# AVRI2CIO_V0_2_LEVEL0.net
KiCad netlist of a schematic drawn in EAGLE
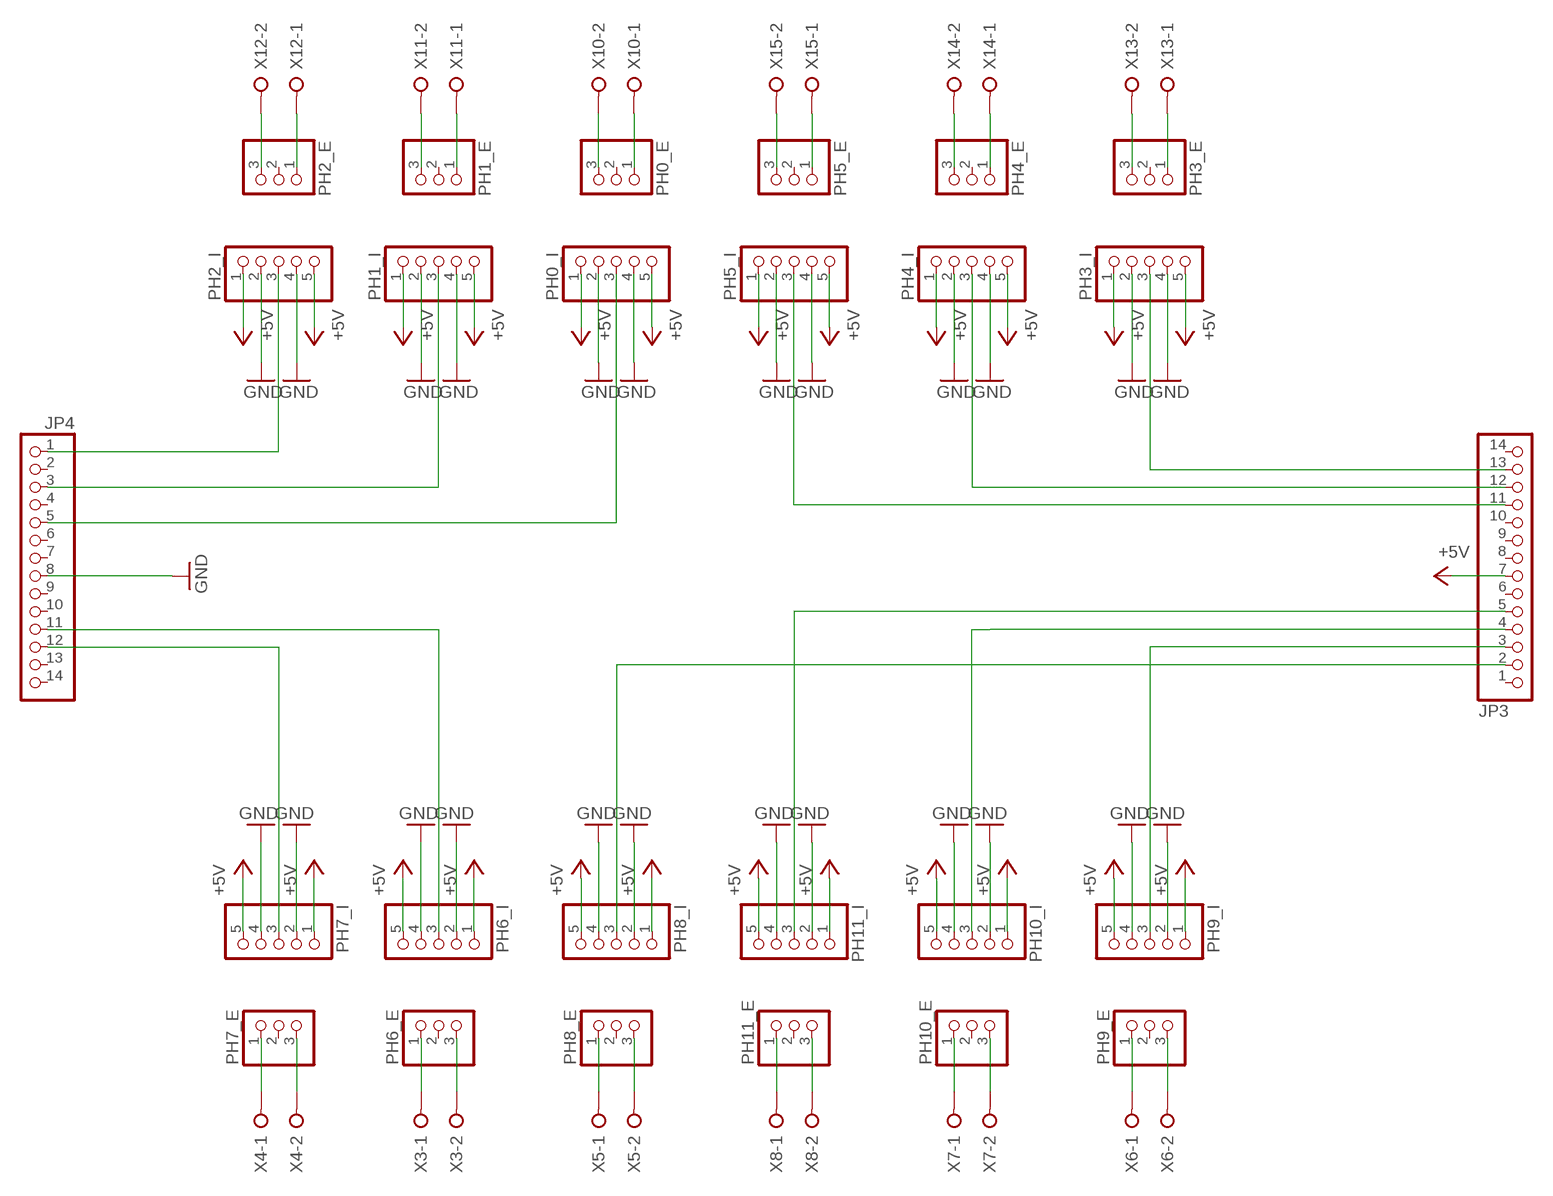
[diagram p0: schematic, sheet 1]

(export (version "E")
  (design (tool "Eeschema 10.0.6"))
  (components
    (comp (ref "JP3")
      (value "PINHD-1X14")
      (footprint "eagle-import:1X14")
      (libsource (lib "eagle-import") (part "PINHD-1X14"))
    )
    (comp (ref "JP4")
      (value "PINHD-1X14")
      (footprint "eagle-import:1X14")
      (libsource (lib "eagle-import") (part "PINHD-1X14"))
    )
    (comp (ref "PH0_E")
      (value "PINHD-1X3")
      (footprint "eagle-import:1X03")
      (libsource (lib "eagle-import") (part "PINHD-1X3"))
    )
    (comp (ref "PH0_I")
      (value "PINHD-1X5")
      (footprint "eagle-import:1X05")
      (libsource (lib "eagle-import") (part "PINHD-1X5"))
    )
    (comp (ref "PH1_E")
      (value "PINHD-1X3")
      (footprint "eagle-import:1X03")
      (libsource (lib "eagle-import") (part "PINHD-1X3"))
    )
    (comp (ref "PH1_I")
      (value "PINHD-1X5")
      (footprint "eagle-import:1X05")
      (libsource (lib "eagle-import") (part "PINHD-1X5"))
    )
    (comp (ref "PH2_E")
      (value "PINHD-1X3")
      (footprint "eagle-import:1X03")
      (libsource (lib "eagle-import") (part "PINHD-1X3"))
    )
    (comp (ref "PH2_I")
      (value "PINHD-1X5")
      (footprint "eagle-import:1X05")
      (libsource (lib "eagle-import") (part "PINHD-1X5"))
    )
    (comp (ref "PH3_E")
      (value "PINHD-1X3")
      (footprint "eagle-import:1X03")
      (libsource (lib "eagle-import") (part "PINHD-1X3"))
    )
    (comp (ref "PH3_I")
      (value "PINHD-1X5")
      (footprint "eagle-import:1X05")
      (libsource (lib "eagle-import") (part "PINHD-1X5"))
    )
    (comp (ref "PH4_E")
      (value "PINHD-1X3")
      (footprint "eagle-import:1X03")
      (libsource (lib "eagle-import") (part "PINHD-1X3"))
    )
    (comp (ref "PH4_I")
      (value "PINHD-1X5")
      (footprint "eagle-import:1X05")
      (libsource (lib "eagle-import") (part "PINHD-1X5"))
    )
    (comp (ref "PH5_E")
      (value "PINHD-1X3")
      (footprint "eagle-import:1X03")
      (libsource (lib "eagle-import") (part "PINHD-1X3"))
    )
    (comp (ref "PH5_I")
      (value "PINHD-1X5")
      (footprint "eagle-import:1X05")
      (libsource (lib "eagle-import") (part "PINHD-1X5"))
    )
    (comp (ref "PH6_E")
      (value "PINHD-1X3")
      (footprint "eagle-import:1X03")
      (libsource (lib "eagle-import") (part "PINHD-1X3"))
    )
    (comp (ref "PH6_I")
      (value "PINHD-1X5")
      (footprint "eagle-import:1X05")
      (libsource (lib "eagle-import") (part "PINHD-1X5"))
    )
    (comp (ref "PH7_E")
      (value "PINHD-1X3")
      (footprint "eagle-import:1X03")
      (libsource (lib "eagle-import") (part "PINHD-1X3"))
    )
    (comp (ref "PH7_I")
      (value "PINHD-1X5")
      (footprint "eagle-import:1X05")
      (libsource (lib "eagle-import") (part "PINHD-1X5"))
    )
    (comp (ref "PH8_E")
      (value "PINHD-1X3")
      (footprint "eagle-import:1X03")
      (libsource (lib "eagle-import") (part "PINHD-1X3"))
    )
    (comp (ref "PH8_I")
      (value "PINHD-1X5")
      (footprint "eagle-import:1X05")
      (libsource (lib "eagle-import") (part "PINHD-1X5"))
    )
    (comp (ref "PH9_E")
      (value "PINHD-1X3")
      (footprint "eagle-import:1X03")
      (libsource (lib "eagle-import") (part "PINHD-1X3"))
    )
    (comp (ref "PH9_I")
      (value "PINHD-1X5")
      (footprint "eagle-import:1X05")
      (libsource (lib "eagle-import") (part "PINHD-1X5"))
    )
    (comp (ref "PH10_E")
      (value "PINHD-1X3")
      (footprint "eagle-import:1X03")
      (libsource (lib "eagle-import") (part "PINHD-1X3"))
    )
    (comp (ref "PH10_I")
      (value "PINHD-1X5")
      (footprint "eagle-import:1X05")
      (libsource (lib "eagle-import") (part "PINHD-1X5"))
    )
    (comp (ref "PH11_E")
      (value "PINHD-1X3")
      (footprint "eagle-import:1X03")
      (libsource (lib "eagle-import") (part "PINHD-1X3"))
    )
    (comp (ref "PH11_I")
      (value "PINHD-1X5")
      (footprint "eagle-import:1X05")
      (libsource (lib "eagle-import") (part "PINHD-1X5"))
    )
    (comp (ref "X3")
      (value "W237-02P")
      (footprint "eagle-import:W237-132")
      (libsource (lib "eagle-import") (part "W237-02P"))
    )
    (comp (ref "X4")
      (value "W237-02P")
      (footprint "eagle-import:W237-132")
      (libsource (lib "eagle-import") (part "W237-02P"))
    )
    (comp (ref "X5")
      (value "W237-02P")
      (footprint "eagle-import:W237-132")
      (libsource (lib "eagle-import") (part "W237-02P"))
    )
    (comp (ref "X6")
      (value "W237-02P")
      (footprint "eagle-import:W237-132")
      (libsource (lib "eagle-import") (part "W237-02P"))
    )
    (comp (ref "X7")
      (value "W237-02P")
      (footprint "eagle-import:W237-132")
      (libsource (lib "eagle-import") (part "W237-02P"))
    )
    (comp (ref "X8")
      (value "W237-02P")
      (footprint "eagle-import:W237-132")
      (libsource (lib "eagle-import") (part "W237-02P"))
    )
    (comp (ref "X10")
      (value "W237-02P")
      (footprint "eagle-import:W237-132")
      (fields (field (name "OC_FARNELL") "unknown"))
      (libsource (lib "eagle-import") (part "W237-02P"))
    )
    (comp (ref "X11")
      (value "W237-02P")
      (footprint "eagle-import:W237-132")
      (libsource (lib "eagle-import") (part "W237-02P"))
    )
    (comp (ref "X12")
      (value "W237-02P")
      (footprint "eagle-import:W237-132")
      (libsource (lib "eagle-import") (part "W237-02P"))
    )
    (comp (ref "X13")
      (value "W237-02P")
      (footprint "eagle-import:W237-132")
      (libsource (lib "eagle-import") (part "W237-02P"))
    )
    (comp (ref "X14")
      (value "W237-02P")
      (footprint "eagle-import:W237-132")
      (libsource (lib "eagle-import") (part "W237-02P"))
    )
    (comp (ref "X15")
      (value "W237-02P")
      (footprint "eagle-import:W237-132")
      (libsource (lib "eagle-import") (part "W237-02P"))
    )
  )
  (nets
    (net (code "1") (name "+5V") (class "Default")
      (node (ref "JP3") (pin "7") (pinfunction "7_7") (pintype "passive"))
      (node (ref "PH0_I") (pin "1") (pinfunction "1_1") (pintype "passive"))
      (node (ref "PH0_I") (pin "5") (pinfunction "5_5") (pintype "passive"))
      (node (ref "PH10_I") (pin "1") (pinfunction "1_1") (pintype "passive"))
      (node (ref "PH10_I") (pin "5") (pinfunction "5_5") (pintype "passive"))
      (node (ref "PH11_I") (pin "1") (pinfunction "1_1") (pintype "passive"))
      (node (ref "PH11_I") (pin "5") (pinfunction "5_5") (pintype "passive"))
      (node (ref "PH1_I") (pin "1") (pinfunction "1_1") (pintype "passive"))
      (node (ref "PH1_I") (pin "5") (pinfunction "5_5") (pintype "passive"))
      (node (ref "PH2_I") (pin "1") (pinfunction "1_1") (pintype "passive"))
      (node (ref "PH2_I") (pin "5") (pinfunction "5_5") (pintype "passive"))
      (node (ref "PH3_I") (pin "1") (pinfunction "1_1") (pintype "passive"))
      (node (ref "PH3_I") (pin "5") (pinfunction "5_5") (pintype "passive"))
      (node (ref "PH4_I") (pin "1") (pinfunction "1_1") (pintype "passive"))
      (node (ref "PH4_I") (pin "5") (pinfunction "5_5") (pintype "passive"))
      (node (ref "PH5_I") (pin "1") (pinfunction "1_1") (pintype "passive"))
      (node (ref "PH5_I") (pin "5") (pinfunction "5_5") (pintype "passive"))
      (node (ref "PH6_I") (pin "1") (pinfunction "1_1") (pintype "passive"))
      (node (ref "PH6_I") (pin "5") (pinfunction "5_5") (pintype "passive"))
      (node (ref "PH7_I") (pin "1") (pinfunction "1_1") (pintype "passive"))
      (node (ref "PH7_I") (pin "5") (pinfunction "5_5") (pintype "passive"))
      (node (ref "PH8_I") (pin "1") (pinfunction "1_1") (pintype "passive"))
      (node (ref "PH8_I") (pin "5") (pinfunction "5_5") (pintype "passive"))
      (node (ref "PH9_I") (pin "1") (pinfunction "1_1") (pintype "passive"))
      (node (ref "PH9_I") (pin "5") (pinfunction "5_5") (pintype "passive"))
    )
    (net (code "2") (name "GND") (class "Default")
      (node (ref "JP4") (pin "8") (pinfunction "8_8") (pintype "passive"))
      (node (ref "PH0_I") (pin "2") (pinfunction "2_2") (pintype "passive"))
      (node (ref "PH0_I") (pin "4") (pinfunction "4_4") (pintype "passive"))
      (node (ref "PH10_I") (pin "2") (pinfunction "2_2") (pintype "passive"))
      (node (ref "PH10_I") (pin "4") (pinfunction "4_4") (pintype "passive"))
      (node (ref "PH11_I") (pin "2") (pinfunction "2_2") (pintype "passive"))
      (node (ref "PH11_I") (pin "4") (pinfunction "4_4") (pintype "passive"))
      (node (ref "PH1_I") (pin "2") (pinfunction "2_2") (pintype "passive"))
      (node (ref "PH1_I") (pin "4") (pinfunction "4_4") (pintype "passive"))
      (node (ref "PH2_I") (pin "2") (pinfunction "2_2") (pintype "passive"))
      (node (ref "PH2_I") (pin "4") (pinfunction "4_4") (pintype "passive"))
      (node (ref "PH3_I") (pin "2") (pinfunction "2_2") (pintype "passive"))
      (node (ref "PH3_I") (pin "4") (pinfunction "4_4") (pintype "passive"))
      (node (ref "PH4_I") (pin "2") (pinfunction "2_2") (pintype "passive"))
      (node (ref "PH4_I") (pin "4") (pinfunction "4_4") (pintype "passive"))
      (node (ref "PH5_I") (pin "2") (pinfunction "2_2") (pintype "passive"))
      (node (ref "PH5_I") (pin "4") (pinfunction "4_4") (pintype "passive"))
      (node (ref "PH6_I") (pin "2") (pinfunction "2_2") (pintype "passive"))
      (node (ref "PH6_I") (pin "4") (pinfunction "4_4") (pintype "passive"))
      (node (ref "PH7_I") (pin "2") (pinfunction "2_2") (pintype "passive"))
      (node (ref "PH7_I") (pin "4") (pinfunction "4_4") (pintype "passive"))
      (node (ref "PH8_I") (pin "2") (pinfunction "2_2") (pintype "passive"))
      (node (ref "PH8_I") (pin "4") (pinfunction "4_4") (pintype "passive"))
      (node (ref "PH9_I") (pin "2") (pinfunction "2_2") (pintype "passive"))
      (node (ref "PH9_I") (pin "4") (pinfunction "4_4") (pintype "passive"))
    )
    (net (code "3") (name "Net-(JP3-Pad2)") (class "Default")
      (node (ref "JP3") (pin "2") (pinfunction "2_2") (pintype "passive"))
      (node (ref "PH8_I") (pin "3") (pinfunction "3_3") (pintype "passive"))
    )
    (net (code "4") (name "Net-(JP3-Pad3)") (class "Default")
      (node (ref "JP3") (pin "3") (pinfunction "3_3") (pintype "passive"))
      (node (ref "PH9_I") (pin "3") (pinfunction "3_3") (pintype "passive"))
    )
    (net (code "5") (name "Net-(JP3-Pad4)") (class "Default")
      (node (ref "JP3") (pin "4") (pinfunction "4_4") (pintype "passive"))
      (node (ref "PH10_I") (pin "3") (pinfunction "3_3") (pintype "passive"))
    )
    (net (code "6") (name "Net-(JP3-Pad5)") (class "Default")
      (node (ref "JP3") (pin "5") (pinfunction "5_5") (pintype "passive"))
      (node (ref "PH11_I") (pin "3") (pinfunction "3_3") (pintype "passive"))
    )
    (net (code "7") (name "Net-(JP3-Pad11)") (class "Default")
      (node (ref "JP3") (pin "11") (pinfunction "11_11") (pintype "passive"))
      (node (ref "PH5_I") (pin "3") (pinfunction "3_3") (pintype "passive"))
    )
    (net (code "8") (name "Net-(JP3-Pad12)") (class "Default")
      (node (ref "JP3") (pin "12") (pinfunction "12_12") (pintype "passive"))
      (node (ref "PH4_I") (pin "3") (pinfunction "3_3") (pintype "passive"))
    )
    (net (code "9") (name "Net-(JP3-Pad13)") (class "Default")
      (node (ref "JP3") (pin "13") (pinfunction "13_13") (pintype "passive"))
      (node (ref "PH3_I") (pin "3") (pinfunction "3_3") (pintype "passive"))
    )
    (net (code "10") (name "Net-(JP4-Pad1)") (class "Default")
      (node (ref "JP4") (pin "1") (pinfunction "1_1") (pintype "passive"))
      (node (ref "PH2_I") (pin "3") (pinfunction "3_3") (pintype "passive"))
    )
    (net (code "11") (name "Net-(JP4-Pad3)") (class "Default")
      (node (ref "JP4") (pin "3") (pinfunction "3_3") (pintype "passive"))
      (node (ref "PH1_I") (pin "3") (pinfunction "3_3") (pintype "passive"))
    )
    (net (code "12") (name "Net-(JP4-Pad5)") (class "Default")
      (node (ref "JP4") (pin "5") (pinfunction "5_5") (pintype "passive"))
      (node (ref "PH0_I") (pin "3") (pinfunction "3_3") (pintype "passive"))
    )
    (net (code "13") (name "Net-(JP4-Pad11)") (class "Default")
      (node (ref "JP4") (pin "11") (pinfunction "11_11") (pintype "passive"))
      (node (ref "PH6_I") (pin "3") (pinfunction "3_3") (pintype "passive"))
    )
    (net (code "14") (name "Net-(JP4-Pad12)") (class "Default")
      (node (ref "JP4") (pin "12") (pinfunction "12_12") (pintype "passive"))
      (node (ref "PH7_I") (pin "3") (pinfunction "3_3") (pintype "passive"))
    )
    (net (code "15") (name "Net-(X3A-KL)") (class "Default")
      (node (ref "PH6_E") (pin "1") (pinfunction "1_1") (pintype "passive"))
      (node (ref "X3") (pin "1") (pinfunction "KL_1") (pintype "passive"))
    )
    (net (code "16") (name "Net-(X3B-KL)") (class "Default")
      (node (ref "PH6_E") (pin "3") (pinfunction "3_3") (pintype "passive"))
      (node (ref "X3") (pin "2") (pinfunction "KL_2") (pintype "passive"))
    )
    (net (code "17") (name "Net-(X4A-KL)") (class "Default")
      (node (ref "PH7_E") (pin "1") (pinfunction "1_1") (pintype "passive"))
      (node (ref "X4") (pin "1") (pinfunction "KL_1") (pintype "passive"))
    )
    (net (code "18") (name "Net-(X4B-KL)") (class "Default")
      (node (ref "PH7_E") (pin "3") (pinfunction "3_3") (pintype "passive"))
      (node (ref "X4") (pin "2") (pinfunction "KL_2") (pintype "passive"))
    )
    (net (code "19") (name "Net-(X5A-KL)") (class "Default")
      (node (ref "PH8_E") (pin "1") (pinfunction "1_1") (pintype "passive"))
      (node (ref "X5") (pin "1") (pinfunction "KL_1") (pintype "passive"))
    )
    (net (code "20") (name "Net-(X5B-KL)") (class "Default")
      (node (ref "PH8_E") (pin "3") (pinfunction "3_3") (pintype "passive"))
      (node (ref "X5") (pin "2") (pinfunction "KL_2") (pintype "passive"))
    )
    (net (code "21") (name "Net-(X6A-KL)") (class "Default")
      (node (ref "PH9_E") (pin "1") (pinfunction "1_1") (pintype "passive"))
      (node (ref "X6") (pin "1") (pinfunction "KL_1") (pintype "passive"))
    )
    (net (code "22") (name "Net-(X6B-KL)") (class "Default")
      (node (ref "PH9_E") (pin "3") (pinfunction "3_3") (pintype "passive"))
      (node (ref "X6") (pin "2") (pinfunction "KL_2") (pintype "passive"))
    )
    (net (code "23") (name "Net-(X7A-KL)") (class "Default")
      (node (ref "PH10_E") (pin "1") (pinfunction "1_1") (pintype "passive"))
      (node (ref "X7") (pin "1") (pinfunction "KL_1") (pintype "passive"))
    )
    (net (code "24") (name "Net-(X7B-KL)") (class "Default")
      (node (ref "PH10_E") (pin "3") (pinfunction "3_3") (pintype "passive"))
      (node (ref "X7") (pin "2") (pinfunction "KL_2") (pintype "passive"))
    )
    (net (code "25") (name "Net-(X8A-KL)") (class "Default")
      (node (ref "PH11_E") (pin "1") (pinfunction "1_1") (pintype "passive"))
      (node (ref "X8") (pin "1") (pinfunction "KL_1") (pintype "passive"))
    )
    (net (code "26") (name "Net-(X8B-KL)") (class "Default")
      (node (ref "PH11_E") (pin "3") (pinfunction "3_3") (pintype "passive"))
      (node (ref "X8") (pin "2") (pinfunction "KL_2") (pintype "passive"))
    )
    (net (code "27") (name "Net-(X10A-KL)") (class "Default")
      (node (ref "PH0_E") (pin "1") (pinfunction "1_1") (pintype "passive"))
      (node (ref "X10") (pin "1") (pinfunction "KL_1") (pintype "passive"))
    )
    (net (code "28") (name "Net-(X10B-KL)") (class "Default")
      (node (ref "PH0_E") (pin "3") (pinfunction "3_3") (pintype "passive"))
      (node (ref "X10") (pin "2") (pinfunction "KL_2") (pintype "passive"))
    )
    (net (code "29") (name "Net-(X11A-KL)") (class "Default")
      (node (ref "PH1_E") (pin "1") (pinfunction "1_1") (pintype "passive"))
      (node (ref "X11") (pin "1") (pinfunction "KL_1") (pintype "passive"))
    )
    (net (code "30") (name "Net-(X11B-KL)") (class "Default")
      (node (ref "PH1_E") (pin "3") (pinfunction "3_3") (pintype "passive"))
      (node (ref "X11") (pin "2") (pinfunction "KL_2") (pintype "passive"))
    )
    (net (code "31") (name "Net-(X12A-KL)") (class "Default")
      (node (ref "PH2_E") (pin "1") (pinfunction "1_1") (pintype "passive"))
      (node (ref "X12") (pin "1") (pinfunction "KL_1") (pintype "passive"))
    )
    (net (code "32") (name "Net-(X12B-KL)") (class "Default")
      (node (ref "PH2_E") (pin "3") (pinfunction "3_3") (pintype "passive"))
      (node (ref "X12") (pin "2") (pinfunction "KL_2") (pintype "passive"))
    )
    (net (code "33") (name "Net-(X13A-KL)") (class "Default")
      (node (ref "PH3_E") (pin "1") (pinfunction "1_1") (pintype "passive"))
      (node (ref "X13") (pin "1") (pinfunction "KL_1") (pintype "passive"))
    )
    (net (code "34") (name "Net-(X13B-KL)") (class "Default")
      (node (ref "PH3_E") (pin "3") (pinfunction "3_3") (pintype "passive"))
      (node (ref "X13") (pin "2") (pinfunction "KL_2") (pintype "passive"))
    )
    (net (code "35") (name "Net-(X14A-KL)") (class "Default")
      (node (ref "PH4_E") (pin "1") (pinfunction "1_1") (pintype "passive"))
      (node (ref "X14") (pin "1") (pinfunction "KL_1") (pintype "passive"))
    )
    (net (code "36") (name "Net-(X14B-KL)") (class "Default")
      (node (ref "PH4_E") (pin "3") (pinfunction "3_3") (pintype "passive"))
      (node (ref "X14") (pin "2") (pinfunction "KL_2") (pintype "passive"))
    )
    (net (code "37") (name "Net-(X15A-KL)") (class "Default")
      (node (ref "PH5_E") (pin "1") (pinfunction "1_1") (pintype "passive"))
      (node (ref "X15") (pin "1") (pinfunction "KL_1") (pintype "passive"))
    )
    (net (code "38") (name "Net-(X15B-KL)") (class "Default")
      (node (ref "PH5_E") (pin "3") (pinfunction "3_3") (pintype "passive"))
      (node (ref "X15") (pin "2") (pinfunction "KL_2") (pintype "passive"))
    )
    (net (code "39") (name "unconnected-(JP3-Pad1)") (class "Default")
      (node (ref "JP3") (pin "1") (pinfunction "1_1") (pintype "passive"))
    )
    (net (code "40") (name "unconnected-(JP3-Pad6)") (class "Default")
      (node (ref "JP3") (pin "6") (pinfunction "6_6") (pintype "passive"))
    )
    (net (code "41") (name "unconnected-(JP3-Pad8)") (class "Default")
      (node (ref "JP3") (pin "8") (pinfunction "8_8") (pintype "passive"))
    )
    (net (code "42") (name "unconnected-(JP3-Pad9)") (class "Default")
      (node (ref "JP3") (pin "9") (pinfunction "9_9") (pintype "passive"))
    )
    (net (code "43") (name "unconnected-(JP3-Pad10)") (class "Default")
      (node (ref "JP3") (pin "10") (pinfunction "10_10") (pintype "passive"))
    )
    (net (code "44") (name "unconnected-(JP3-Pad14)") (class "Default")
      (node (ref "JP3") (pin "14") (pinfunction "14_14") (pintype "passive"))
    )
    (net (code "45") (name "unconnected-(JP4-Pad2)") (class "Default")
      (node (ref "JP4") (pin "2") (pinfunction "2_2") (pintype "passive"))
    )
    (net (code "46") (name "unconnected-(JP4-Pad4)") (class "Default")
      (node (ref "JP4") (pin "4") (pinfunction "4_4") (pintype "passive"))
    )
    (net (code "47") (name "unconnected-(JP4-Pad6)") (class "Default")
      (node (ref "JP4") (pin "6") (pinfunction "6_6") (pintype "passive"))
    )
    (net (code "48") (name "unconnected-(JP4-Pad7)") (class "Default")
      (node (ref "JP4") (pin "7") (pinfunction "7_7") (pintype "passive"))
    )
    (net (code "49") (name "unconnected-(JP4-Pad9)") (class "Default")
      (node (ref "JP4") (pin "9") (pinfunction "9_9") (pintype "passive"))
    )
    (net (code "50") (name "unconnected-(JP4-Pad10)") (class "Default")
      (node (ref "JP4") (pin "10") (pinfunction "10_10") (pintype "passive"))
    )
    (net (code "51") (name "unconnected-(JP4-Pad13)") (class "Default")
      (node (ref "JP4") (pin "13") (pinfunction "13_13") (pintype "passive"))
    )
    (net (code "52") (name "unconnected-(JP4-Pad14)") (class "Default")
      (node (ref "JP4") (pin "14") (pinfunction "14_14") (pintype "passive"))
    )
    (net (code "53") (name "unconnected-(PH0_E-Pad2)") (class "Default")
      (node (ref "PH0_E") (pin "2") (pinfunction "2_2") (pintype "passive"))
    )
    (net (code "54") (name "unconnected-(PH1_E-Pad2)") (class "Default")
      (node (ref "PH1_E") (pin "2") (pinfunction "2_2") (pintype "passive"))
    )
    (net (code "55") (name "unconnected-(PH2_E-Pad2)") (class "Default")
      (node (ref "PH2_E") (pin "2") (pinfunction "2_2") (pintype "passive"))
    )
    (net (code "56") (name "unconnected-(PH3_E-Pad2)") (class "Default")
      (node (ref "PH3_E") (pin "2") (pinfunction "2_2") (pintype "passive"))
    )
    (net (code "57") (name "unconnected-(PH4_E-Pad2)") (class "Default")
      (node (ref "PH4_E") (pin "2") (pinfunction "2_2") (pintype "passive"))
    )
    (net (code "58") (name "unconnected-(PH5_E-Pad2)") (class "Default")
      (node (ref "PH5_E") (pin "2") (pinfunction "2_2") (pintype "passive"))
    )
    (net (code "59") (name "unconnected-(PH6_E-Pad2)") (class "Default")
      (node (ref "PH6_E") (pin "2") (pinfunction "2_2") (pintype "passive"))
    )
    (net (code "60") (name "unconnected-(PH7_E-Pad2)") (class "Default")
      (node (ref "PH7_E") (pin "2") (pinfunction "2_2") (pintype "passive"))
    )
    (net (code "61") (name "unconnected-(PH8_E-Pad2)") (class "Default")
      (node (ref "PH8_E") (pin "2") (pinfunction "2_2") (pintype "passive"))
    )
    (net (code "62") (name "unconnected-(PH9_E-Pad2)") (class "Default")
      (node (ref "PH9_E") (pin "2") (pinfunction "2_2") (pintype "passive"))
    )
    (net (code "63") (name "unconnected-(PH10_E-Pad2)") (class "Default")
      (node (ref "PH10_E") (pin "2") (pinfunction "2_2") (pintype "passive"))
    )
    (net (code "64") (name "unconnected-(PH11_E-Pad2)") (class "Default")
      (node (ref "PH11_E") (pin "2") (pinfunction "2_2") (pintype "passive"))
    )
  )
)
